# vr-glove-circuit-sch.net
KiCad netlist of a schematic drawn in EAGLE
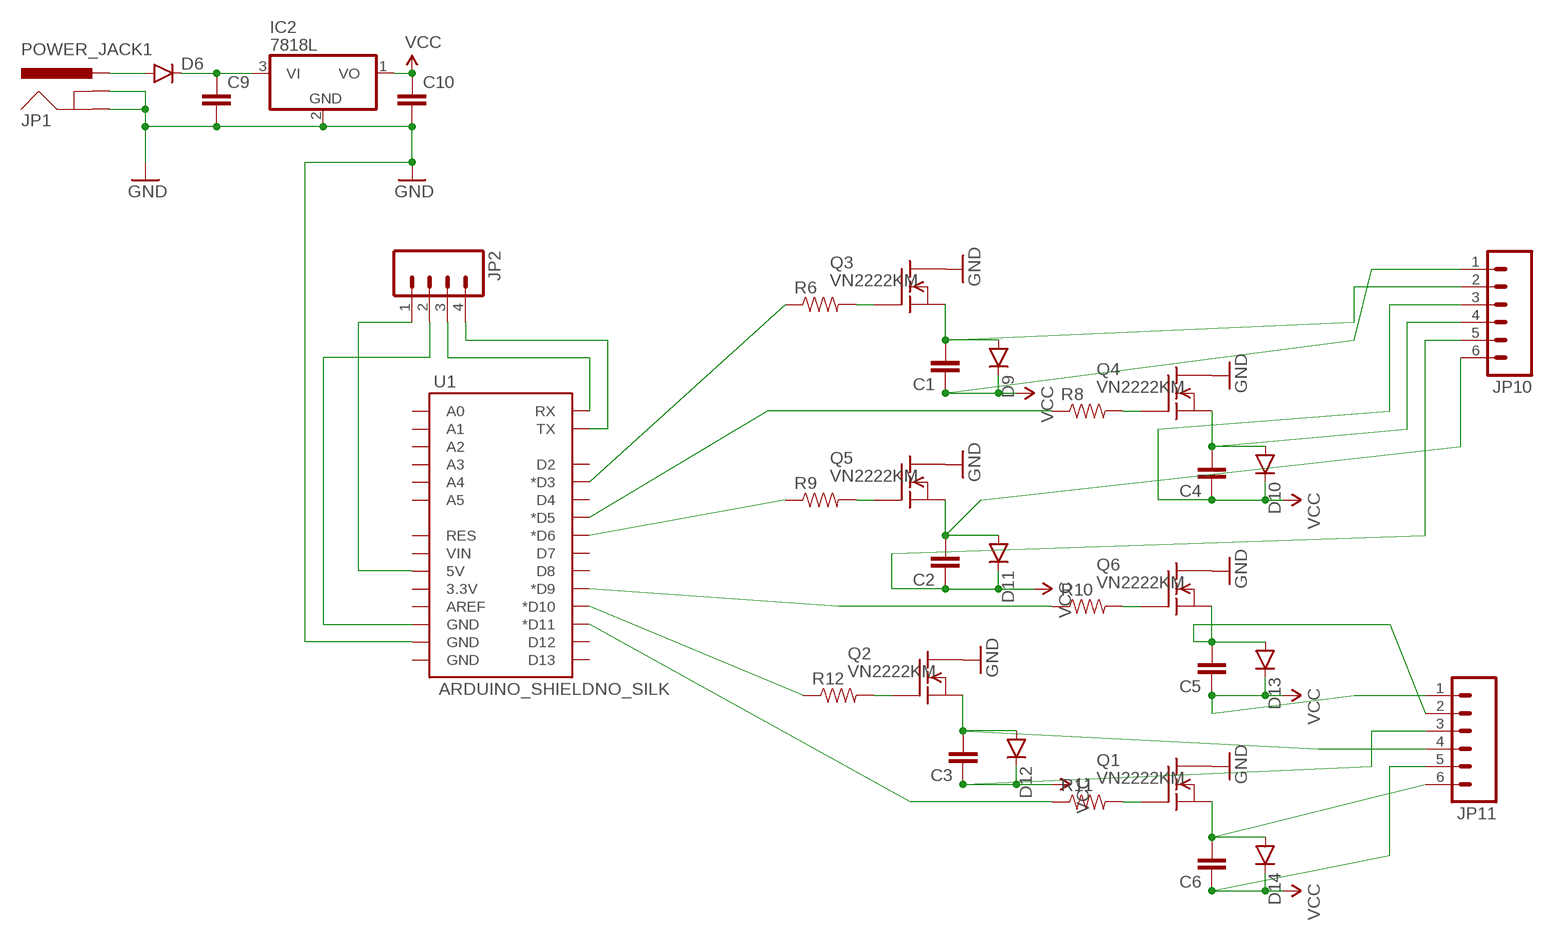
[diagram p0: schematic, sheet 1]

(export (version "E")
  (design (tool "Eeschema 10.0.6"))
  (components
    (comp (ref "C1")
      (value "CAPPTH")
      (footprint "eagle-import:CAP-PTH-SMALL")
      (libsource (lib "eagle-import") (part "CAPPTH"))
    )
    (comp (ref "C2")
      (value "CAPPTH")
      (footprint "eagle-import:CAP-PTH-SMALL")
      (libsource (lib "eagle-import") (part "CAPPTH"))
    )
    (comp (ref "C3")
      (value "CAPPTH")
      (footprint "eagle-import:CAP-PTH-SMALL")
      (libsource (lib "eagle-import") (part "CAPPTH"))
    )
    (comp (ref "C4")
      (value "CAPPTH")
      (footprint "eagle-import:CAP-PTH-SMALL")
      (libsource (lib "eagle-import") (part "CAPPTH"))
    )
    (comp (ref "C5")
      (value "CAPPTH")
      (footprint "eagle-import:CAP-PTH-SMALL")
      (libsource (lib "eagle-import") (part "CAPPTH"))
    )
    (comp (ref "C6")
      (value "CAPPTH")
      (footprint "eagle-import:CAP-PTH-SMALL")
      (libsource (lib "eagle-import") (part "CAPPTH"))
    )
    (comp (ref "C9")
      (value "CAPPTH")
      (footprint "eagle-import:CAP-PTH-SMALL")
      (libsource (lib "eagle-import") (part "SparkFun-Passives_CAPPTH"))
    )
    (comp (ref "C10")
      (value "CAPPTH")
      (footprint "eagle-import:CAP-PTH-SMALL")
      (libsource (lib "eagle-import") (part "SparkFun-Passives_CAPPTH"))
    )
    (comp (ref "D6")
      (value "DIODE1N4148")
      (footprint "eagle-import:DIODE-1N4148")
      (libsource (lib "eagle-import") (part "DIODE1N4148"))
    )
    (comp (ref "D9")
      (value "DIODE1N4148")
      (footprint "eagle-import:DIODE-1N4148")
      (libsource (lib "eagle-import") (part "DIODE1N4148"))
    )
    (comp (ref "D10")
      (value "DIODE1N4148")
      (footprint "eagle-import:DIODE-1N4148")
      (libsource (lib "eagle-import") (part "DIODE1N4148"))
    )
    (comp (ref "D11")
      (value "DIODE1N4148")
      (footprint "eagle-import:DIODE-1N4148")
      (libsource (lib "eagle-import") (part "DIODE1N4148"))
    )
    (comp (ref "D12")
      (value "DIODE1N4148")
      (footprint "eagle-import:DIODE-1N4148")
      (libsource (lib "eagle-import") (part "DIODE1N4148"))
    )
    (comp (ref "D13")
      (value "DIODE1N4148")
      (footprint "eagle-import:DIODE-1N4148")
      (libsource (lib "eagle-import") (part "DIODE1N4148"))
    )
    (comp (ref "D14")
      (value "DIODE1N4148")
      (footprint "eagle-import:DIODE-1N4148")
      (libsource (lib "eagle-import") (part "DIODE1N4148"))
    )
    (comp (ref "IC2")
      (value "7818L")
      (footprint "eagle-import:TO92")
      (libsource (lib "eagle-import") (part "78L18"))
    )
    (comp (ref "JP1")
      (value "POWER_JACK1")
      (footprint "eagle-import:POWER_JACK_SMD_OVERPASTE_REDBOARD_0603")
      (libsource (lib "eagle-import") (part "POWER_JACK1"))
    )
    (comp (ref "JP2")
      (value "M04LOCK")
      (footprint "eagle-import:1X04_LOCK")
      (libsource (lib "eagle-import") (part "M04LOCK"))
    )
    (comp (ref "JP10")
      (value "M06SILK_FEMALE_PTH")
      (footprint "eagle-import:1X06")
      (libsource (lib "eagle-import") (part "M06SILK_FEMALE_PTH"))
    )
    (comp (ref "JP11")
      (value "M06SILK_FEMALE_PTH")
      (footprint "eagle-import:1X06")
      (libsource (lib "eagle-import") (part "M06SILK_FEMALE_PTH"))
    )
    (comp (ref "Q1")
      (value "VN2222KM")
      (footprint "eagle-import:TO237")
      (libsource (lib "eagle-import") (part "VN2222KM"))
    )
    (comp (ref "Q2")
      (value "VN2222KM")
      (footprint "eagle-import:TO237")
      (libsource (lib "eagle-import") (part "VN2222KM"))
    )
    (comp (ref "Q3")
      (value "VN2222KM")
      (footprint "eagle-import:TO237")
      (libsource (lib "eagle-import") (part "VN2222KM"))
    )
    (comp (ref "Q4")
      (value "VN2222KM")
      (footprint "eagle-import:TO237")
      (libsource (lib "eagle-import") (part "VN2222KM"))
    )
    (comp (ref "Q5")
      (value "VN2222KM")
      (footprint "eagle-import:TO237")
      (libsource (lib "eagle-import") (part "VN2222KM"))
    )
    (comp (ref "Q6")
      (value "VN2222KM")
      (footprint "eagle-import:TO237")
      (libsource (lib "eagle-import") (part "VN2222KM"))
    )
    (comp (ref "R6")
      (value "RESISTORPTH-1/4W-VERT")
      (footprint "eagle-import:AXIAL-0.1")
      (libsource (lib "eagle-import") (part "RESISTORPTH-1/4W-VERT"))
    )
    (comp (ref "R8")
      (value "RESISTORPTH-1/4W-VERT")
      (footprint "eagle-import:AXIAL-0.1")
      (libsource (lib "eagle-import") (part "RESISTORPTH-1/4W-VERT"))
    )
    (comp (ref "R9")
      (value "RESISTORPTH-1/4W-VERT")
      (footprint "eagle-import:AXIAL-0.1")
      (libsource (lib "eagle-import") (part "RESISTORPTH-1/4W-VERT"))
    )
    (comp (ref "R10")
      (value "RESISTORPTH-1/4W-VERT")
      (footprint "eagle-import:AXIAL-0.1")
      (libsource (lib "eagle-import") (part "RESISTORPTH-1/4W-VERT"))
    )
    (comp (ref "R11")
      (value "RESISTORPTH-1/4W-VERT")
      (footprint "eagle-import:AXIAL-0.1")
      (libsource (lib "eagle-import") (part "RESISTORPTH-1/4W-VERT"))
    )
    (comp (ref "R12")
      (value "RESISTORPTH-1/4W-VERT")
      (footprint "eagle-import:AXIAL-0.1")
      (libsource (lib "eagle-import") (part "RESISTORPTH-1/4W-VERT"))
    )
    (comp (ref "U1")
      (value "ARDUINO_SHIELDNO_SILK")
      (footprint "eagle-import:DUEMILANOVE_VIAS")
      (libsource (lib "eagle-import") (part "ARDUINO_SHIELDNO_SILK"))
    )
  )
  (nets
    (net (code "1") (name "GND") (class "Default")
      (node (ref "C10") (pin "2") (pinfunction "2_2") (pintype "passive"))
      (node (ref "C9") (pin "2") (pinfunction "2_2") (pintype "passive"))
      (node (ref "IC2") (pin "2") (pinfunction "GND_2") (pintype "passive"))
      (node (ref "JP1") (pin "GND") (pinfunction "GNDBREAK_GND") (pintype "bidirectional"))
      (node (ref "JP1") (pin "P$4") (pinfunction "GND_P$4") (pintype "bidirectional"))
      (node (ref "Q1") (pin "1") (pinfunction "D_1") (pintype "passive"))
      (node (ref "Q2") (pin "1") (pinfunction "D_1") (pintype "passive"))
      (node (ref "Q3") (pin "1") (pinfunction "D_1") (pintype "passive"))
      (node (ref "Q4") (pin "1") (pinfunction "D_1") (pintype "passive"))
      (node (ref "Q5") (pin "1") (pinfunction "D_1") (pintype "passive"))
      (node (ref "Q6") (pin "1") (pinfunction "D_1") (pintype "passive"))
      (node (ref "U1") (pin "GND@1") (pinfunction "GND_GND@1") (pintype "bidirectional"))
    )
    (net (code "2") (name "Net-(IC2-VI)") (class "Default")
      (node (ref "C9") (pin "1") (pinfunction "1_1") (pintype "passive"))
      (node (ref "D6") (pin "C") (pinfunction "C_C") (pintype "passive"))
      (node (ref "IC2") (pin "3") (pinfunction "VI_3") (pintype "input"))
    )
    (net (code "3") (name "Net-(JP1-PWR)") (class "Default")
      (node (ref "D6") (pin "A") (pinfunction "A_A") (pintype "passive"))
      (node (ref "JP1") (pin "VIN0") (pinfunction "PWR_VIN0") (pintype "bidirectional"))
    )
    (net (code "4") (name "Net-(JP2-Pad1)") (class "Default")
      (node (ref "JP2") (pin "1") (pinfunction "1_1") (pintype "passive"))
      (node (ref "U1") (pin "5V") (pinfunction "5V_5V") (pintype "bidirectional"))
    )
    (net (code "5") (name "Net-(JP2-Pad2)") (class "Default")
      (node (ref "JP2") (pin "2") (pinfunction "2_2") (pintype "passive"))
      (node (ref "U1") (pin "GND@2") (pinfunction "GND_GND@2") (pintype "bidirectional"))
    )
    (net (code "6") (name "Net-(JP2-Pad3)") (class "Default")
      (node (ref "JP2") (pin "3") (pinfunction "3_3") (pintype "passive"))
      (node (ref "U1") (pin "RX") (pinfunction "RX_RX") (pintype "bidirectional"))
    )
    (net (code "7") (name "Net-(JP2-Pad4)") (class "Default")
      (node (ref "JP2") (pin "4") (pinfunction "4_4") (pintype "passive"))
      (node (ref "U1") (pin "TX") (pinfunction "TX_TX") (pintype "bidirectional"))
    )
    (net (code "8") (name "Net-(Q1-G)") (class "Default")
      (node (ref "Q1") (pin "2") (pinfunction "G_2") (pintype "passive"))
      (node (ref "R11") (pin "P$2") (pinfunction "2_P$2") (pintype "passive"))
    )
    (net (code "9") (name "Net-(Q1-S)") (class "Default")
      (node (ref "C6") (pin "2") (pinfunction "2_2") (pintype "passive"))
      (node (ref "D14") (pin "A") (pinfunction "A_A") (pintype "passive"))
      (node (ref "JP11") (pin "6") (pinfunction "6_6") (pintype "passive"))
      (node (ref "Q1") (pin "3") (pinfunction "S_3") (pintype "passive"))
    )
    (net (code "10") (name "Net-(Q2-G)") (class "Default")
      (node (ref "Q2") (pin "2") (pinfunction "G_2") (pintype "passive"))
      (node (ref "R12") (pin "P$2") (pinfunction "2_P$2") (pintype "passive"))
    )
    (net (code "11") (name "Net-(Q2-S)") (class "Default")
      (node (ref "C3") (pin "2") (pinfunction "2_2") (pintype "passive"))
      (node (ref "D12") (pin "A") (pinfunction "A_A") (pintype "passive"))
      (node (ref "JP11") (pin "4") (pinfunction "4_4") (pintype "passive"))
      (node (ref "Q2") (pin "3") (pinfunction "S_3") (pintype "passive"))
    )
    (net (code "12") (name "Net-(Q3-G)") (class "Default")
      (node (ref "Q3") (pin "2") (pinfunction "G_2") (pintype "passive"))
      (node (ref "R6") (pin "P$2") (pinfunction "2_P$2") (pintype "passive"))
    )
    (net (code "13") (name "Net-(Q3-S)") (class "Default")
      (node (ref "C1") (pin "2") (pinfunction "2_2") (pintype "passive"))
      (node (ref "D9") (pin "A") (pinfunction "A_A") (pintype "passive"))
      (node (ref "JP10") (pin "2") (pinfunction "2_2") (pintype "passive"))
      (node (ref "Q3") (pin "3") (pinfunction "S_3") (pintype "passive"))
    )
    (net (code "14") (name "Net-(Q4-G)") (class "Default")
      (node (ref "Q4") (pin "2") (pinfunction "G_2") (pintype "passive"))
      (node (ref "R8") (pin "P$2") (pinfunction "2_P$2") (pintype "passive"))
    )
    (net (code "15") (name "Net-(Q4-S)") (class "Default")
      (node (ref "C4") (pin "2") (pinfunction "2_2") (pintype "passive"))
      (node (ref "D10") (pin "A") (pinfunction "A_A") (pintype "passive"))
      (node (ref "JP10") (pin "4") (pinfunction "4_4") (pintype "passive"))
      (node (ref "Q4") (pin "3") (pinfunction "S_3") (pintype "passive"))
    )
    (net (code "16") (name "Net-(Q5-G)") (class "Default")
      (node (ref "Q5") (pin "2") (pinfunction "G_2") (pintype "passive"))
      (node (ref "R9") (pin "P$2") (pinfunction "2_P$2") (pintype "passive"))
    )
    (net (code "17") (name "Net-(Q5-S)") (class "Default")
      (node (ref "C2") (pin "2") (pinfunction "2_2") (pintype "passive"))
      (node (ref "D11") (pin "A") (pinfunction "A_A") (pintype "passive"))
      (node (ref "JP10") (pin "6") (pinfunction "6_6") (pintype "passive"))
      (node (ref "Q5") (pin "3") (pinfunction "S_3") (pintype "passive"))
    )
    (net (code "18") (name "Net-(Q6-G)") (class "Default")
      (node (ref "Q6") (pin "2") (pinfunction "G_2") (pintype "passive"))
      (node (ref "R10") (pin "P$2") (pinfunction "2_P$2") (pintype "passive"))
    )
    (net (code "19") (name "Net-(Q6-S)") (class "Default")
      (node (ref "C5") (pin "2") (pinfunction "2_2") (pintype "passive"))
      (node (ref "D13") (pin "A") (pinfunction "A_A") (pintype "passive"))
      (node (ref "JP11") (pin "2") (pinfunction "2_2") (pintype "passive"))
      (node (ref "Q6") (pin "3") (pinfunction "S_3") (pintype "passive"))
    )
    (net (code "20") (name "Net-(R6-1)") (class "Default")
      (node (ref "R6") (pin "P$1") (pinfunction "1_P$1") (pintype "passive"))
      (node (ref "U1") (pin "D3") (pinfunction "*D3_D3") (pintype "bidirectional"))
    )
    (net (code "21") (name "Net-(R8-1)") (class "Default")
      (node (ref "R8") (pin "P$1") (pinfunction "1_P$1") (pintype "passive"))
      (node (ref "U1") (pin "D5") (pinfunction "*D5_D5") (pintype "bidirectional"))
    )
    (net (code "22") (name "Net-(R9-1)") (class "Default")
      (node (ref "R9") (pin "P$1") (pinfunction "1_P$1") (pintype "passive"))
      (node (ref "U1") (pin "D6") (pinfunction "*D6_D6") (pintype "bidirectional"))
    )
    (net (code "23") (name "Net-(R10-1)") (class "Default")
      (node (ref "R10") (pin "P$1") (pinfunction "1_P$1") (pintype "passive"))
      (node (ref "U1") (pin "D9") (pinfunction "*D9_D9") (pintype "bidirectional"))
    )
    (net (code "24") (name "Net-(R11-1)") (class "Default")
      (node (ref "R11") (pin "P$1") (pinfunction "1_P$1") (pintype "passive"))
      (node (ref "U1") (pin "D11") (pinfunction "*D11_D11") (pintype "bidirectional"))
    )
    (net (code "25") (name "Net-(R12-1)") (class "Default")
      (node (ref "R12") (pin "P$1") (pinfunction "1_P$1") (pintype "passive"))
      (node (ref "U1") (pin "D10") (pinfunction "*D10_D10") (pintype "bidirectional"))
    )
    (net (code "26") (name "VCC") (class "Default")
      (node (ref "C1") (pin "1") (pinfunction "1_1") (pintype "passive"))
      (node (ref "C10") (pin "1") (pinfunction "1_1") (pintype "passive"))
      (node (ref "C2") (pin "1") (pinfunction "1_1") (pintype "passive"))
      (node (ref "C3") (pin "1") (pinfunction "1_1") (pintype "passive"))
      (node (ref "C4") (pin "1") (pinfunction "1_1") (pintype "passive"))
      (node (ref "C5") (pin "1") (pinfunction "1_1") (pintype "passive"))
      (node (ref "C6") (pin "1") (pinfunction "1_1") (pintype "passive"))
      (node (ref "D10") (pin "C") (pinfunction "C_C") (pintype "passive"))
      (node (ref "D11") (pin "C") (pinfunction "C_C") (pintype "passive"))
      (node (ref "D12") (pin "C") (pinfunction "C_C") (pintype "passive"))
      (node (ref "D13") (pin "C") (pinfunction "C_C") (pintype "passive"))
      (node (ref "D14") (pin "C") (pinfunction "C_C") (pintype "passive"))
      (node (ref "D9") (pin "C") (pinfunction "C_C") (pintype "passive"))
      (node (ref "IC2") (pin "1") (pinfunction "VO_1") (pintype "passive"))
      (node (ref "JP10") (pin "1") (pinfunction "1_1") (pintype "passive"))
      (node (ref "JP10") (pin "3") (pinfunction "3_3") (pintype "passive"))
      (node (ref "JP10") (pin "5") (pinfunction "5_5") (pintype "passive"))
      (node (ref "JP11") (pin "1") (pinfunction "1_1") (pintype "passive"))
      (node (ref "JP11") (pin "3") (pinfunction "3_3") (pintype "passive"))
      (node (ref "JP11") (pin "5") (pinfunction "5_5") (pintype "passive"))
    )
    (net (code "27") (name "unconnected-(U1-GND-PadGND@0)") (class "Default")
      (node (ref "U1") (pin "GND@0") (pinfunction "GND_GND@0") (pintype "bidirectional"))
    )
    (net (code "28") (name "unconnected-(U1-Pad3.3V)") (class "Default")
      (node (ref "U1") (pin "3.3V") (pinfunction "3.3V_3.3V") (pintype "bidirectional"))
    )
    (net (code "29") (name "unconnected-(U1-PadA0)") (class "Default")
      (node (ref "U1") (pin "A0") (pinfunction "A0_A0") (pintype "bidirectional"))
    )
    (net (code "30") (name "unconnected-(U1-PadA1)") (class "Default")
      (node (ref "U1") (pin "A1") (pinfunction "A1_A1") (pintype "bidirectional"))
    )
    (net (code "31") (name "unconnected-(U1-PadA2)") (class "Default")
      (node (ref "U1") (pin "A2") (pinfunction "A2_A2") (pintype "bidirectional"))
    )
    (net (code "32") (name "unconnected-(U1-PadA3)") (class "Default")
      (node (ref "U1") (pin "A3") (pinfunction "A3_A3") (pintype "bidirectional"))
    )
    (net (code "33") (name "unconnected-(U1-PadA4)") (class "Default")
      (node (ref "U1") (pin "A4") (pinfunction "A4_A4") (pintype "bidirectional"))
    )
    (net (code "34") (name "unconnected-(U1-PadA5)") (class "Default")
      (node (ref "U1") (pin "A5") (pinfunction "A5_A5") (pintype "bidirectional"))
    )
    (net (code "35") (name "unconnected-(U1-PadAREF)") (class "Default")
      (node (ref "U1") (pin "AREF") (pinfunction "AREF_AREF") (pintype "bidirectional"))
    )
    (net (code "36") (name "unconnected-(U1-PadD2)") (class "Default")
      (node (ref "U1") (pin "D2") (pinfunction "D2_D2") (pintype "bidirectional"))
    )
    (net (code "37") (name "unconnected-(U1-PadD4)") (class "Default")
      (node (ref "U1") (pin "D4") (pinfunction "D4_D4") (pintype "bidirectional"))
    )
    (net (code "38") (name "unconnected-(U1-PadD7)") (class "Default")
      (node (ref "U1") (pin "D7") (pinfunction "D7_D7") (pintype "bidirectional"))
    )
    (net (code "39") (name "unconnected-(U1-PadD8)") (class "Default")
      (node (ref "U1") (pin "D8") (pinfunction "D8_D8") (pintype "bidirectional"))
    )
    (net (code "40") (name "unconnected-(U1-PadD12)") (class "Default")
      (node (ref "U1") (pin "D12") (pinfunction "D12_D12") (pintype "bidirectional"))
    )
    (net (code "41") (name "unconnected-(U1-PadD13)") (class "Default")
      (node (ref "U1") (pin "D13") (pinfunction "D13_D13") (pintype "bidirectional"))
    )
    (net (code "42") (name "unconnected-(U1-PadRES)") (class "Default")
      (node (ref "U1") (pin "RES") (pinfunction "RES_RES") (pintype "bidirectional"))
    )
    (net (code "43") (name "unconnected-(U1-PadVIN)") (class "Default")
      (node (ref "U1") (pin "VIN") (pinfunction "VIN_VIN") (pintype "bidirectional"))
    )
  )
)
